# Suino_board.net
KiCad netlist of a schematic drawn in EAGLE
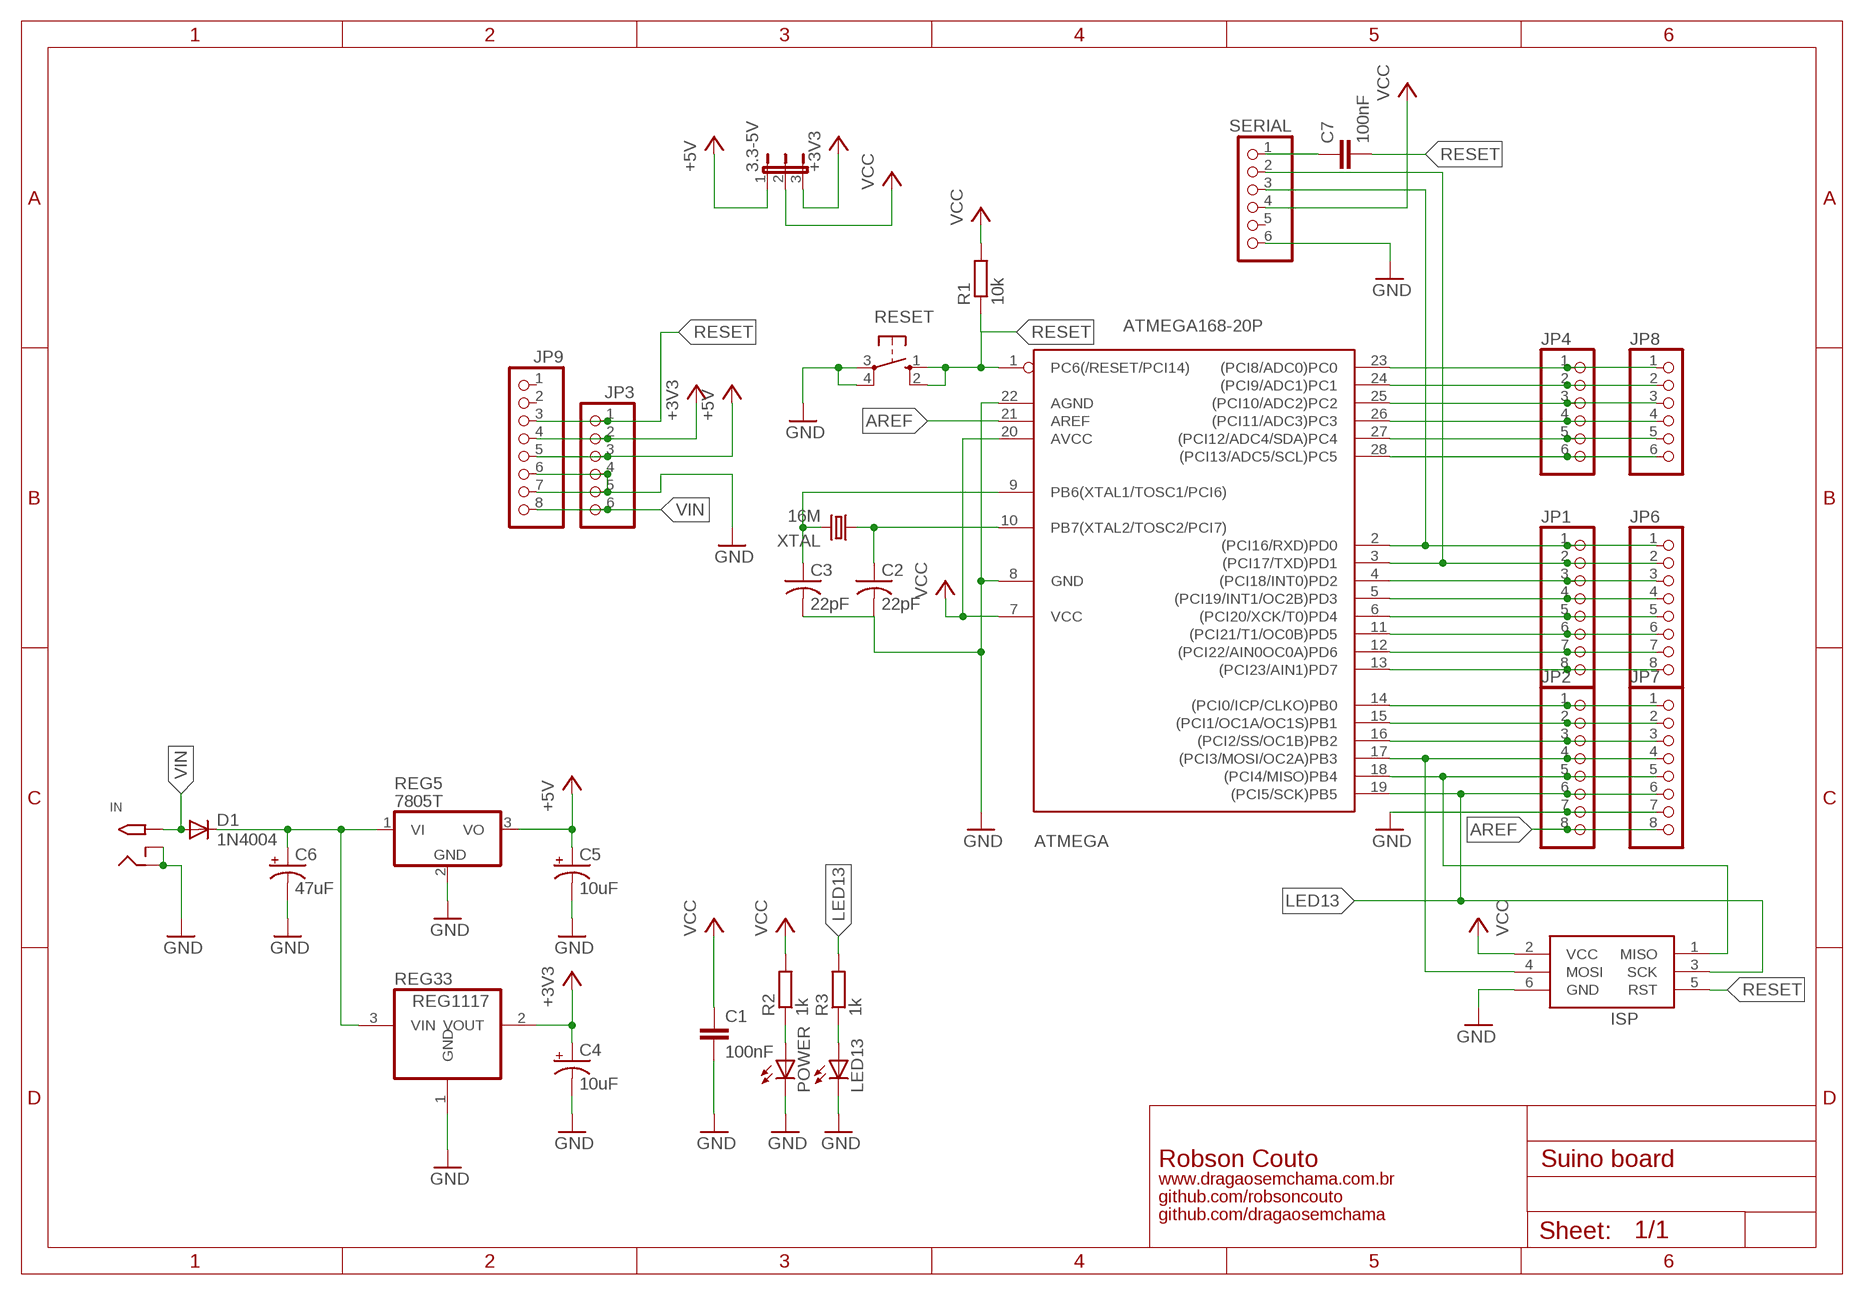
[diagram p0: schematic, sheet 1]

(export (version "E")
  (design (tool "Eeschema 10.0.6"))
  (components
    (comp (ref "3.3-5V")
      (value "JP2E")
      (footprint "eagle-import:JP2")
      (libsource (lib "eagle-import") (part "JP2E"))
    )
    (comp (ref "ATMEGA")
      (value "ATMEGA168-20P")
      (footprint "eagle-import:DIL28-3")
      (libsource (lib "eagle-import") (part "ATMEGA168P-20"))
    )
    (comp (ref "C1")
      (value "100nF")
      (footprint "eagle-import:C050-025X075")
      (libsource (lib "eagle-import") (part "C-EU050-025X075"))
    )
    (comp (ref "C2")
      (value "22pF")
      (footprint "eagle-import:C025-030X050")
      (libsource (lib "eagle-import") (part "C-US025-030X050"))
    )
    (comp (ref "C3")
      (value "22pF")
      (footprint "eagle-import:C025-030X050")
      (libsource (lib "eagle-import") (part "C-US025-030X050"))
    )
    (comp (ref "C4")
      (value "10uF")
      (footprint "eagle-import:E2,5-5")
      (libsource (lib "eagle-import") (part "CPOL-USE2.5-5"))
    )
    (comp (ref "C5")
      (value "10uF")
      (footprint "eagle-import:E2,5-5")
      (libsource (lib "eagle-import") (part "CPOL-USE2.5-5"))
    )
    (comp (ref "C6")
      (value "47uF")
      (footprint "eagle-import:E2,5-6")
      (libsource (lib "eagle-import") (part "CPOL-USE2.5-6"))
    )
    (comp (ref "C7")
      (value "100nF")
      (footprint "eagle-import:C050-025X075")
      (libsource (lib "eagle-import") (part "C-EU050-025X075"))
    )
    (comp (ref "D1")
      (value "1N4004")
      (footprint "eagle-import:DO41-10")
      (libsource (lib "eagle-import") (part "1N4004"))
    )
    (comp (ref "IN")
      (value "2.1MMJACKTHM")
      (footprint "eagle-import:PJ-102A")
      (libsource (lib "eagle-import") (part "2.1MMJACKTHM"))
    )
    (comp (ref "ISP")
      (value "AVRISP-6")
      (footprint "eagle-import:AVRISP")
      (libsource (lib "eagle-import") (part "AVRISP-6"))
    )
    (comp (ref "JP1")
      (value "PINHD-1X8BIG")
      (footprint "eagle-import:1X08-BIG")
      (libsource (lib "eagle-import") (part "PINHD-1X8BIG"))
    )
    (comp (ref "JP2")
      (value "PINHD-1X8BIG")
      (footprint "eagle-import:1X08-BIG")
      (libsource (lib "eagle-import") (part "PINHD-1X8BIG"))
    )
    (comp (ref "JP3")
      (value "PINHD-1X6B")
      (footprint "eagle-import:1X06-BIG")
      (libsource (lib "eagle-import") (part "PINHD-1X6B"))
    )
    (comp (ref "JP4")
      (value "PINHD-1X6B")
      (footprint "eagle-import:1X06-BIG")
      (libsource (lib "eagle-import") (part "PINHD-1X6B"))
    )
    (comp (ref "JP6")
      (value "PINHD-1X8BIG")
      (footprint "eagle-import:1X08-BIG")
      (libsource (lib "eagle-import") (part "PINHD-1X8BIG"))
    )
    (comp (ref "JP7")
      (value "PINHD-1X8BIG")
      (footprint "eagle-import:1X08-BIG")
      (libsource (lib "eagle-import") (part "PINHD-1X8BIG"))
    )
    (comp (ref "JP8")
      (value "PINHD-1X6B")
      (footprint "eagle-import:1X06-BIG")
      (libsource (lib "eagle-import") (part "PINHD-1X6B"))
    )
    (comp (ref "JP9")
      (value "PINHD-1X8BIG")
      (footprint "eagle-import:1X08-BIG")
      (libsource (lib "eagle-import") (part "PINHD-1X8BIG"))
    )
    (comp (ref "LED13")
      (value "LED3MM")
      (footprint "eagle-import:LED3MM")
      (libsource (lib "eagle-import") (part "LED3MM"))
    )
    (comp (ref "POWER")
      (value "LED3MM")
      (footprint "eagle-import:LED3MM")
      (libsource (lib "eagle-import") (part "LED3MM"))
    )
    (comp (ref "R1")
      (value "10k")
      (footprint "eagle-import:0207_7")
      (libsource (lib "eagle-import") (part "R-EU_0207/7"))
    )
    (comp (ref "R2")
      (value "1k")
      (footprint "eagle-import:0207_7")
      (libsource (lib "eagle-import") (part "R-EU_0207/7"))
    )
    (comp (ref "R3")
      (value "1k")
      (footprint "eagle-import:0207_7")
      (libsource (lib "eagle-import") (part "R-EU_0207/7"))
    )
    (comp (ref "REG5")
      (value "7805T")
      (footprint "eagle-import:TO220H")
      (libsource (lib "eagle-import") (part "78T05"))
    )
    (comp (ref "REG33")
      (value "REG1117")
      (footprint "eagle-import:SOT223")
      (libsource (lib "eagle-import") (part "REG1117"))
    )
    (comp (ref "RESET")
      (value "10-XX")
      (footprint "eagle-import:B3F-10XX")
      (fields (field (name "MPN") "B3F-1000"))
      (libsource (lib "eagle-import") (part "10-XX"))
    )
    (comp (ref "SERIAL")
      (value "PINHD-1X6")
      (footprint "eagle-import:1X06")
      (libsource (lib "eagle-import") (part "PINHD-1X6"))
    )
    (comp (ref "XTAL")
      (value "16M")
      (footprint "eagle-import:HC49_S")
      (libsource (lib "eagle-import") (part "CRYSTALHC49S"))
    )
  )
  (nets
    (net (code "1") (name "+3V3") (class "Default")
      (node (ref "3.3-5V") (pin "3") (pinfunction "3_3") (pintype "passive"))
      (node (ref "C4") (pin "+") (pinfunction "+_+") (pintype "passive"))
      (node (ref "JP3") (pin "2") (pinfunction "2_2") (pintype "passive"))
      (node (ref "JP9") (pin "4") (pinfunction "4_4") (pintype "passive"))
      (node (ref "REG33") (pin "2") (pinfunction "VOUT_2") (pintype "output"))
    )
    (net (code "2") (name "+5V") (class "Default")
      (node (ref "3.3-5V") (pin "1") (pinfunction "1_1") (pintype "passive"))
      (node (ref "C5") (pin "+") (pinfunction "+_+") (pintype "passive"))
      (node (ref "JP3") (pin "3") (pinfunction "3_3") (pintype "passive"))
      (node (ref "JP9") (pin "5") (pinfunction "5_5") (pintype "passive"))
      (node (ref "REG5") (pin "3") (pinfunction "VO_3") (pintype "passive"))
    )
    (net (code "3") (name "AREF") (class "Default")
      (node (ref "ATMEGA") (pin "21") (pinfunction "AREF_21") (pintype "bidirectional"))
      (node (ref "JP2") (pin "8") (pinfunction "8_8") (pintype "passive"))
      (node (ref "JP7") (pin "8") (pinfunction "8_8") (pintype "passive"))
    )
    (net (code "4") (name "GND") (class "Default")
      (node (ref "ATMEGA") (pin "22") (pinfunction "AGND_22") (pintype "bidirectional"))
      (node (ref "ATMEGA") (pin "8") (pinfunction "GND_8") (pintype "bidirectional"))
      (node (ref "C1") (pin "2") (pinfunction "2_2") (pintype "passive"))
      (node (ref "C2") (pin "2") (pinfunction "2_2") (pintype "passive"))
      (node (ref "C3") (pin "2") (pinfunction "2_2") (pintype "passive"))
      (node (ref "C4") (pin "-") (pinfunction "-_-") (pintype "passive"))
      (node (ref "C5") (pin "-") (pinfunction "-_-") (pintype "passive"))
      (node (ref "C6") (pin "-") (pinfunction "-_-") (pintype "passive"))
      (node (ref "IN") (pin "RING") (pinfunction "RING_RING") (pintype "bidirectional"))
      (node (ref "IN") (pin "RING_SW") (pinfunction "RING_SW_RING_SW") (pintype "bidirectional"))
      (node (ref "ISP") (pin "6") (pinfunction "GND_6") (pintype "power_in"))
      (node (ref "JP2") (pin "7") (pinfunction "7_7") (pintype "passive"))
      (node (ref "JP3") (pin "4") (pinfunction "4_4") (pintype "passive"))
      (node (ref "JP3") (pin "5") (pinfunction "5_5") (pintype "passive"))
      (node (ref "JP7") (pin "7") (pinfunction "7_7") (pintype "passive"))
      (node (ref "JP9") (pin "6") (pinfunction "6_6") (pintype "passive"))
      (node (ref "JP9") (pin "7") (pinfunction "7_7") (pintype "passive"))
      (node (ref "LED13") (pin "K") (pinfunction "C_K") (pintype "passive"))
      (node (ref "POWER") (pin "K") (pinfunction "C_K") (pintype "passive"))
      (node (ref "REG33") (pin "1") (pinfunction "GND_1") (pintype "power_in"))
      (node (ref "REG5") (pin "2") (pinfunction "GND_2") (pintype "passive"))
      (node (ref "RESET") (pin "3") (pinfunction "P_3") (pintype "passive"))
      (node (ref "RESET") (pin "4") (pinfunction "P1_4") (pintype "passive"))
      (node (ref "SERIAL") (pin "6") (pinfunction "6_6") (pintype "passive"))
    )
    (net (code "5") (name "LED13") (class "Default")
      (node (ref "ATMEGA") (pin "19") (pinfunction "(PCI5/SCK)PB5_19") (pintype "bidirectional"))
      (node (ref "ISP") (pin "3") (pinfunction "SCK_3") (pintype "output"))
      (node (ref "JP2") (pin "6") (pinfunction "6_6") (pintype "passive"))
      (node (ref "JP7") (pin "6") (pinfunction "6_6") (pintype "passive"))
      (node (ref "R3") (pin "2") (pinfunction "2_2") (pintype "passive"))
    )
    (net (code "6") (name "Net-(ATMEGA-(PCI0{slash}ICP{slash}CLKO)PB0)") (class "Default")
      (node (ref "ATMEGA") (pin "14") (pinfunction "(PCI0/ICP/CLKO)PB0_14") (pintype "bidirectional"))
      (node (ref "JP2") (pin "1") (pinfunction "1_1") (pintype "passive"))
      (node (ref "JP7") (pin "1") (pinfunction "1_1") (pintype "passive"))
    )
    (net (code "7") (name "Net-(ATMEGA-(PCI1{slash}OC1A{slash}OC1S)PB1)") (class "Default")
      (node (ref "ATMEGA") (pin "15") (pinfunction "(PCI1/OC1A/OC1S)PB1_15") (pintype "bidirectional"))
      (node (ref "JP2") (pin "2") (pinfunction "2_2") (pintype "passive"))
      (node (ref "JP7") (pin "2") (pinfunction "2_2") (pintype "passive"))
    )
    (net (code "8") (name "Net-(ATMEGA-(PCI2{slash}SS{slash}OC1B)PB2)") (class "Default")
      (node (ref "ATMEGA") (pin "16") (pinfunction "(PCI2/SS/OC1B)PB2_16") (pintype "bidirectional"))
      (node (ref "JP2") (pin "3") (pinfunction "3_3") (pintype "passive"))
      (node (ref "JP7") (pin "3") (pinfunction "3_3") (pintype "passive"))
    )
    (net (code "9") (name "Net-(ATMEGA-(PCI3{slash}MOSI{slash}OC2A)PB3)") (class "Default")
      (node (ref "ATMEGA") (pin "17") (pinfunction "(PCI3/MOSI/OC2A)PB3_17") (pintype "bidirectional"))
      (node (ref "ISP") (pin "4") (pinfunction "MOSI_4") (pintype "output"))
      (node (ref "JP2") (pin "4") (pinfunction "4_4") (pintype "passive"))
      (node (ref "JP7") (pin "4") (pinfunction "4_4") (pintype "passive"))
    )
    (net (code "10") (name "Net-(ATMEGA-(PCI4{slash}MISO)PB4)") (class "Default")
      (node (ref "ATMEGA") (pin "18") (pinfunction "(PCI4/MISO)PB4_18") (pintype "bidirectional"))
      (node (ref "ISP") (pin "1") (pinfunction "MISO_1") (pintype "input"))
      (node (ref "JP2") (pin "5") (pinfunction "5_5") (pintype "passive"))
      (node (ref "JP7") (pin "5") (pinfunction "5_5") (pintype "passive"))
    )
    (net (code "11") (name "Net-(ATMEGA-(PCI8{slash}ADC0)PC0)") (class "Default")
      (node (ref "ATMEGA") (pin "23") (pinfunction "(PCI8/ADC0)PC0_23") (pintype "bidirectional"))
      (node (ref "JP4") (pin "1") (pinfunction "1_1") (pintype "passive"))
      (node (ref "JP8") (pin "1") (pinfunction "1_1") (pintype "passive"))
    )
    (net (code "12") (name "Net-(ATMEGA-(PCI9{slash}ADC1)PC1)") (class "Default")
      (node (ref "ATMEGA") (pin "24") (pinfunction "(PCI9/ADC1)PC1_24") (pintype "bidirectional"))
      (node (ref "JP4") (pin "2") (pinfunction "2_2") (pintype "passive"))
      (node (ref "JP8") (pin "2") (pinfunction "2_2") (pintype "passive"))
    )
    (net (code "13") (name "Net-(ATMEGA-(PCI10{slash}ADC2)PC2)") (class "Default")
      (node (ref "ATMEGA") (pin "25") (pinfunction "(PCI10/ADC2)PC2_25") (pintype "bidirectional"))
      (node (ref "JP4") (pin "3") (pinfunction "3_3") (pintype "passive"))
      (node (ref "JP8") (pin "3") (pinfunction "3_3") (pintype "passive"))
    )
    (net (code "14") (name "Net-(ATMEGA-(PCI11{slash}ADC3)PC3)") (class "Default")
      (node (ref "ATMEGA") (pin "26") (pinfunction "(PCI11/ADC3)PC3_26") (pintype "bidirectional"))
      (node (ref "JP4") (pin "4") (pinfunction "4_4") (pintype "passive"))
      (node (ref "JP8") (pin "4") (pinfunction "4_4") (pintype "passive"))
    )
    (net (code "15") (name "Net-(ATMEGA-(PCI12{slash}ADC4{slash}SDA)PC4)") (class "Default")
      (node (ref "ATMEGA") (pin "27") (pinfunction "(PCI12/ADC4/SDA)PC4_27") (pintype "bidirectional"))
      (node (ref "JP4") (pin "5") (pinfunction "5_5") (pintype "passive"))
      (node (ref "JP8") (pin "5") (pinfunction "5_5") (pintype "passive"))
    )
    (net (code "16") (name "Net-(ATMEGA-(PCI13{slash}ADC5{slash}SCL)PC5)") (class "Default")
      (node (ref "ATMEGA") (pin "28") (pinfunction "(PCI13/ADC5/SCL)PC5_28") (pintype "bidirectional"))
      (node (ref "JP4") (pin "6") (pinfunction "6_6") (pintype "passive"))
      (node (ref "JP8") (pin "6") (pinfunction "6_6") (pintype "passive"))
    )
    (net (code "17") (name "Net-(ATMEGA-(PCI16{slash}RXD)PD0)") (class "Default")
      (node (ref "ATMEGA") (pin "2") (pinfunction "(PCI16/RXD)PD0_2") (pintype "bidirectional"))
      (node (ref "JP1") (pin "1") (pinfunction "1_1") (pintype "passive"))
      (node (ref "JP6") (pin "1") (pinfunction "1_1") (pintype "passive"))
      (node (ref "SERIAL") (pin "3") (pinfunction "3_3") (pintype "passive"))
    )
    (net (code "18") (name "Net-(ATMEGA-(PCI17{slash}TXD)PD1)") (class "Default")
      (node (ref "ATMEGA") (pin "3") (pinfunction "(PCI17/TXD)PD1_3") (pintype "bidirectional"))
      (node (ref "JP1") (pin "2") (pinfunction "2_2") (pintype "passive"))
      (node (ref "JP6") (pin "2") (pinfunction "2_2") (pintype "passive"))
      (node (ref "SERIAL") (pin "2") (pinfunction "2_2") (pintype "passive"))
    )
    (net (code "19") (name "Net-(ATMEGA-(PCI18{slash}INT0)PD2)") (class "Default")
      (node (ref "ATMEGA") (pin "4") (pinfunction "(PCI18/INT0)PD2_4") (pintype "bidirectional"))
      (node (ref "JP1") (pin "3") (pinfunction "3_3") (pintype "passive"))
      (node (ref "JP6") (pin "3") (pinfunction "3_3") (pintype "passive"))
    )
    (net (code "20") (name "Net-(ATMEGA-(PCI19{slash}INT1{slash}OC2B)PD3)") (class "Default")
      (node (ref "ATMEGA") (pin "5") (pinfunction "(PCI19/INT1/OC2B)PD3_5") (pintype "bidirectional"))
      (node (ref "JP1") (pin "4") (pinfunction "4_4") (pintype "passive"))
      (node (ref "JP6") (pin "4") (pinfunction "4_4") (pintype "passive"))
    )
    (net (code "21") (name "Net-(ATMEGA-(PCI20{slash}XCK{slash}T0)PD4)") (class "Default")
      (node (ref "ATMEGA") (pin "6") (pinfunction "(PCI20/XCK/T0)PD4_6") (pintype "bidirectional"))
      (node (ref "JP1") (pin "5") (pinfunction "5_5") (pintype "passive"))
      (node (ref "JP6") (pin "5") (pinfunction "5_5") (pintype "passive"))
    )
    (net (code "22") (name "Net-(ATMEGA-(PCI21{slash}T1{slash}OC0B)PD5)") (class "Default")
      (node (ref "ATMEGA") (pin "11") (pinfunction "(PCI21/T1/OC0B)PD5_11") (pintype "bidirectional"))
      (node (ref "JP1") (pin "6") (pinfunction "6_6") (pintype "passive"))
      (node (ref "JP6") (pin "6") (pinfunction "6_6") (pintype "passive"))
    )
    (net (code "23") (name "Net-(ATMEGA-(PCI22{slash}AIN0OC0A)PD6)") (class "Default")
      (node (ref "ATMEGA") (pin "12") (pinfunction "(PCI22/AIN0OC0A)PD6_12") (pintype "bidirectional"))
      (node (ref "JP1") (pin "7") (pinfunction "7_7") (pintype "passive"))
      (node (ref "JP6") (pin "7") (pinfunction "7_7") (pintype "passive"))
    )
    (net (code "24") (name "Net-(ATMEGA-(PCI23{slash}AIN1)PD7)") (class "Default")
      (node (ref "ATMEGA") (pin "13") (pinfunction "(PCI23/AIN1)PD7_13") (pintype "bidirectional"))
      (node (ref "JP1") (pin "8") (pinfunction "8_8") (pintype "passive"))
      (node (ref "JP6") (pin "8") (pinfunction "8_8") (pintype "passive"))
    )
    (net (code "25") (name "Net-(ATMEGA-PB6(XTAL1{slash}TOSC1{slash}PCI6))") (class "Default")
      (node (ref "ATMEGA") (pin "9") (pinfunction "PB6(XTAL1/TOSC1/PCI6)_9") (pintype "bidirectional"))
      (node (ref "C3") (pin "1") (pinfunction "1_1") (pintype "passive"))
      (node (ref "XTAL") (pin "2") (pinfunction "2_2") (pintype "passive"))
    )
    (net (code "26") (name "Net-(ATMEGA-PB7(XTAL2{slash}TOSC2{slash}PCI7))") (class "Default")
      (node (ref "ATMEGA") (pin "10") (pinfunction "PB7(XTAL2/TOSC2/PCI7)_10") (pintype "bidirectional"))
      (node (ref "C2") (pin "1") (pinfunction "1_1") (pintype "passive"))
      (node (ref "XTAL") (pin "1") (pinfunction "1_1") (pintype "passive"))
    )
    (net (code "27") (name "Net-(C7-Pad1)") (class "Default")
      (node (ref "C7") (pin "1") (pinfunction "1_1") (pintype "passive"))
      (node (ref "SERIAL") (pin "1") (pinfunction "1_1") (pintype "passive"))
    )
    (net (code "28") (name "Net-(LED13-PadA)") (class "Default")
      (node (ref "LED13") (pin "A") (pinfunction "A_A") (pintype "passive"))
      (node (ref "R3") (pin "1") (pinfunction "1_1") (pintype "passive"))
    )
    (net (code "29") (name "Net-(POWER-PadA)") (class "Default")
      (node (ref "POWER") (pin "A") (pinfunction "A_A") (pintype "passive"))
      (node (ref "R2") (pin "1") (pinfunction "1_1") (pintype "passive"))
    )
    (net (code "30") (name "Net-(REG33-VIN)") (class "Default")
      (node (ref "C6") (pin "+") (pinfunction "+_+") (pintype "passive"))
      (node (ref "D1") (pin "C") (pinfunction "C_C") (pintype "passive"))
      (node (ref "REG33") (pin "3") (pinfunction "VIN_3") (pintype "input"))
      (node (ref "REG5") (pin "1") (pinfunction "VI_1") (pintype "input"))
    )
    (net (code "31") (name "RESET") (class "Default")
      (node (ref "ATMEGA") (pin "1") (pinfunction "PC6(/RESET/PCI14)_1") (pintype "bidirectional"))
      (node (ref "C7") (pin "2") (pinfunction "2_2") (pintype "passive"))
      (node (ref "ISP") (pin "5") (pinfunction "RST_5") (pintype "output"))
      (node (ref "JP3") (pin "1") (pinfunction "1_1") (pintype "passive"))
      (node (ref "JP9") (pin "3") (pinfunction "3_3") (pintype "passive"))
      (node (ref "R1") (pin "1") (pinfunction "1_1") (pintype "passive"))
      (node (ref "RESET") (pin "1") (pinfunction "S_1") (pintype "passive"))
      (node (ref "RESET") (pin "2") (pinfunction "S1_2") (pintype "passive"))
    )
    (net (code "32") (name "VCC") (class "Default")
      (node (ref "3.3-5V") (pin "2") (pinfunction "2_2") (pintype "passive"))
      (node (ref "ATMEGA") (pin "20") (pinfunction "AVCC_20") (pintype "bidirectional"))
      (node (ref "ATMEGA") (pin "7") (pinfunction "VCC_7") (pintype "bidirectional"))
      (node (ref "C1") (pin "1") (pinfunction "1_1") (pintype "passive"))
      (node (ref "ISP") (pin "2") (pinfunction "VCC_2") (pintype "power_in"))
      (node (ref "R1") (pin "2") (pinfunction "2_2") (pintype "passive"))
      (node (ref "R2") (pin "2") (pinfunction "2_2") (pintype "passive"))
      (node (ref "SERIAL") (pin "4") (pinfunction "4_4") (pintype "passive"))
    )
    (net (code "33") (name "VIN") (class "Default")
      (node (ref "D1") (pin "A") (pinfunction "A_A") (pintype "passive"))
      (node (ref "IN") (pin "TIP") (pinfunction "TIP_TIP") (pintype "bidirectional"))
      (node (ref "JP3") (pin "6") (pinfunction "6_6") (pintype "passive"))
      (node (ref "JP9") (pin "8") (pinfunction "8_8") (pintype "passive"))
    )
    (net (code "34") (name "unconnected-(JP9-Pad1)") (class "Default")
      (node (ref "JP9") (pin "1") (pinfunction "1_1") (pintype "passive"))
    )
    (net (code "35") (name "unconnected-(JP9-Pad2)") (class "Default")
      (node (ref "JP9") (pin "2") (pinfunction "2_2") (pintype "passive"))
    )
    (net (code "36") (name "unconnected-(SERIAL-Pad5)") (class "Default")
      (node (ref "SERIAL") (pin "5") (pinfunction "5_5") (pintype "passive"))
    )
  )
)
